# RPi_Color_Detector_LED_PCB_v2.net
KiCad netlist of a schematic drawn in EAGLE
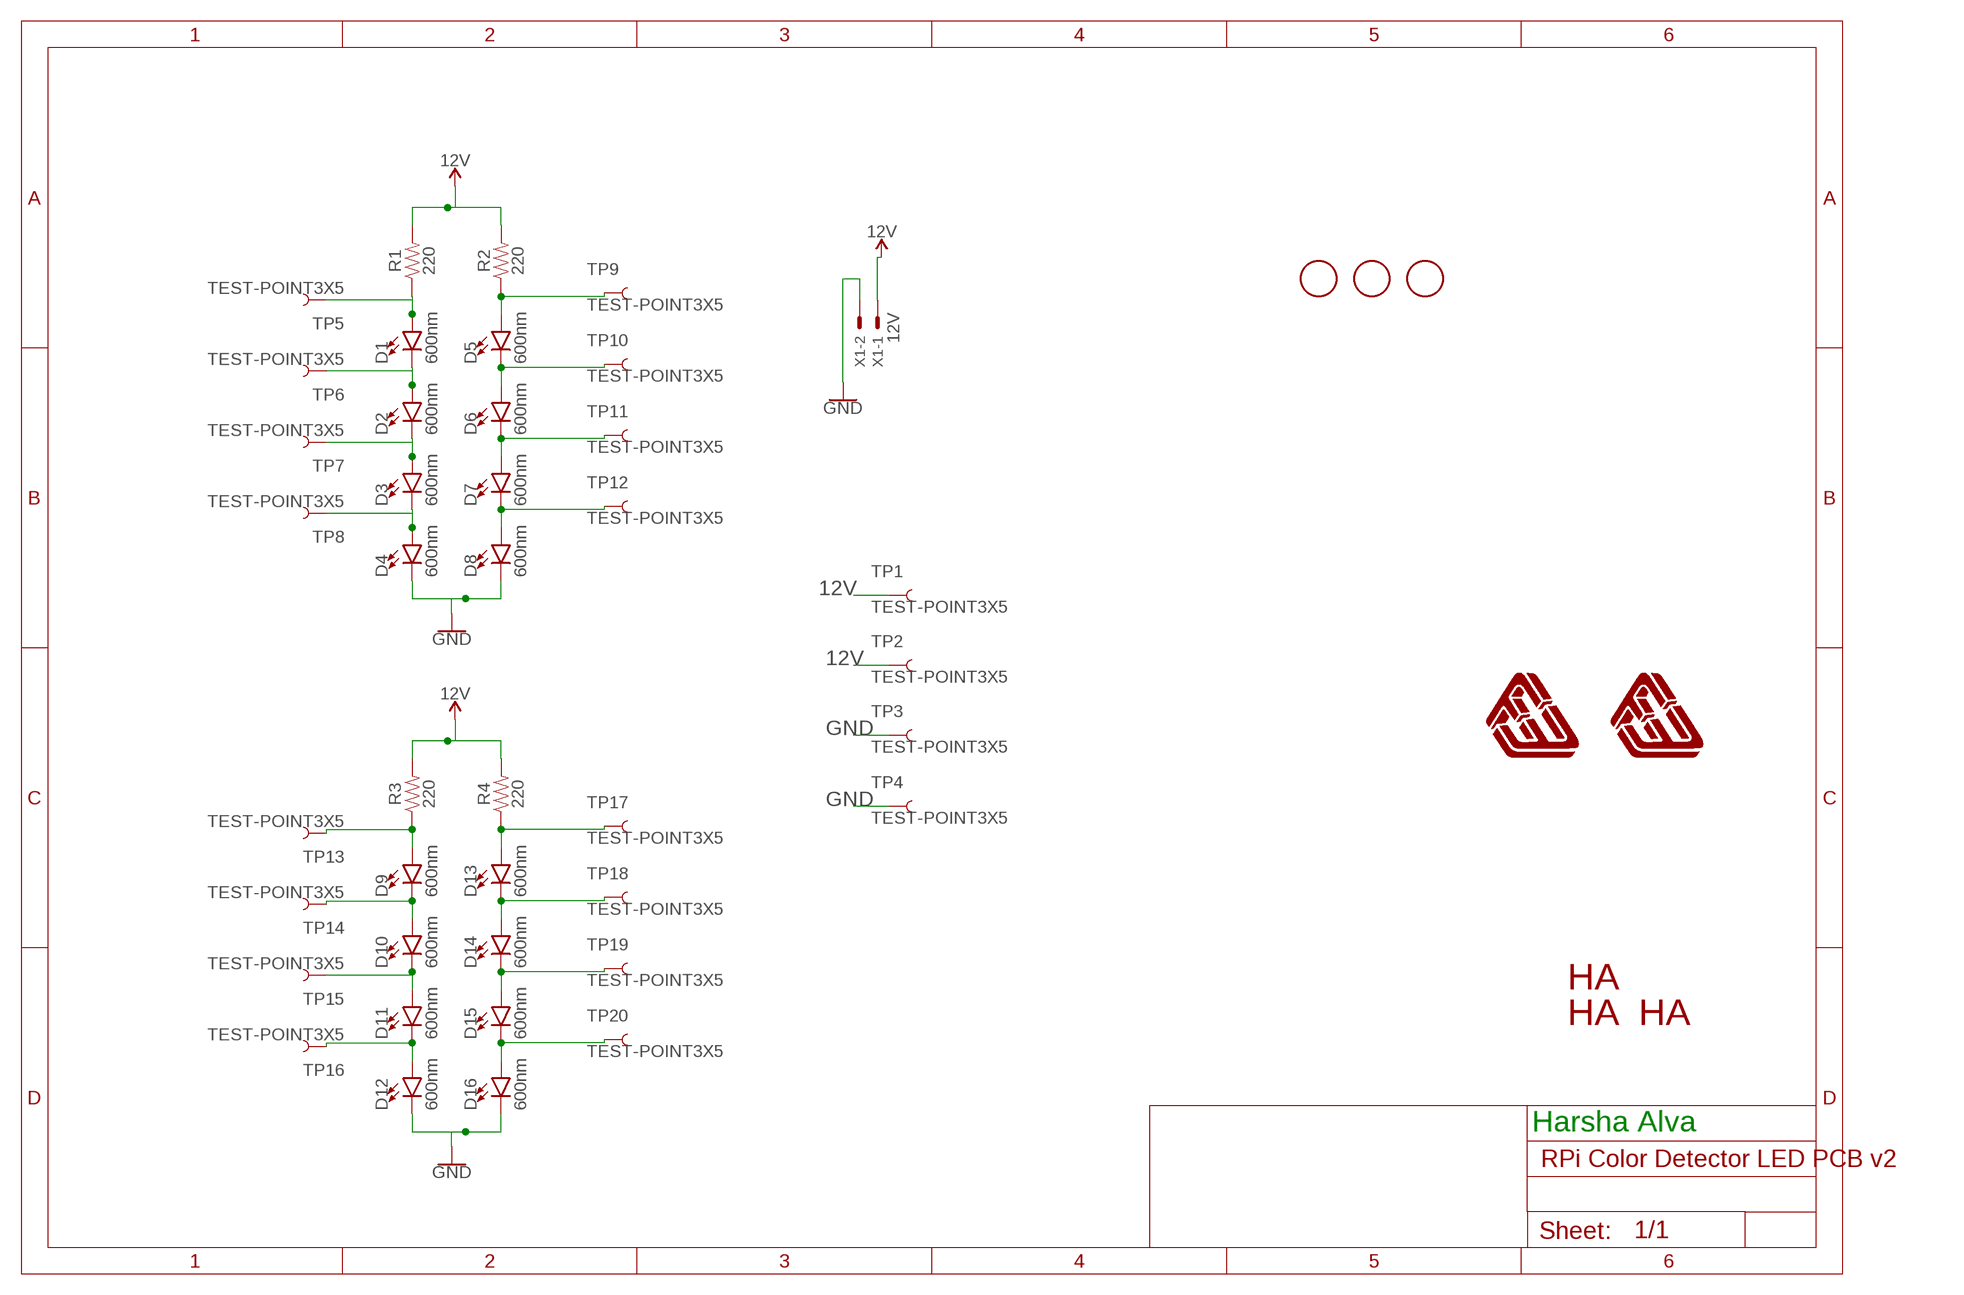
[diagram p0: schematic, sheet 1]

(export (version "E")
  (design (tool "Eeschema 10.0.6"))
  (components
    (comp (ref "D1")
      (value "600nm")
      (footprint "eagle-import:LED-0603")
      (libsource (lib "eagle-import") (part "LED-GREEN0603"))
    )
    (comp (ref "D2")
      (value "600nm")
      (footprint "eagle-import:LED-0603")
      (libsource (lib "eagle-import") (part "LED-GREEN0603"))
    )
    (comp (ref "D3")
      (value "600nm")
      (footprint "eagle-import:LED-0603")
      (libsource (lib "eagle-import") (part "LED-GREEN0603"))
    )
    (comp (ref "D4")
      (value "600nm")
      (footprint "eagle-import:LED-0603")
      (libsource (lib "eagle-import") (part "LED-GREEN0603"))
    )
    (comp (ref "D5")
      (value "600nm")
      (footprint "eagle-import:LED-0603")
      (libsource (lib "eagle-import") (part "LED-GREEN0603"))
    )
    (comp (ref "D6")
      (value "600nm")
      (footprint "eagle-import:LED-0603")
      (libsource (lib "eagle-import") (part "LED-GREEN0603"))
    )
    (comp (ref "D7")
      (value "600nm")
      (footprint "eagle-import:LED-0603")
      (libsource (lib "eagle-import") (part "LED-GREEN0603"))
    )
    (comp (ref "D8")
      (value "600nm")
      (footprint "eagle-import:LED-0603")
      (libsource (lib "eagle-import") (part "LED-GREEN0603"))
    )
    (comp (ref "D9")
      (value "600nm")
      (footprint "eagle-import:LED-0603")
      (libsource (lib "eagle-import") (part "LED-GREEN0603"))
    )
    (comp (ref "D10")
      (value "600nm")
      (footprint "eagle-import:LED-0603")
      (libsource (lib "eagle-import") (part "LED-GREEN0603"))
    )
    (comp (ref "D11")
      (value "600nm")
      (footprint "eagle-import:LED-0603")
      (libsource (lib "eagle-import") (part "LED-GREEN0603"))
    )
    (comp (ref "D12")
      (value "600nm")
      (footprint "eagle-import:LED-0603")
      (libsource (lib "eagle-import") (part "LED-GREEN0603"))
    )
    (comp (ref "D13")
      (value "600nm")
      (footprint "eagle-import:LED-0603")
      (libsource (lib "eagle-import") (part "LED-GREEN0603"))
    )
    (comp (ref "D14")
      (value "600nm")
      (footprint "eagle-import:LED-0603")
      (libsource (lib "eagle-import") (part "LED-GREEN0603"))
    )
    (comp (ref "D15")
      (value "600nm")
      (footprint "eagle-import:LED-0603")
      (libsource (lib "eagle-import") (part "LED-GREEN0603"))
    )
    (comp (ref "D16")
      (value "600nm")
      (footprint "eagle-import:LED-0603")
      (libsource (lib "eagle-import") (part "LED-GREEN0603"))
    )
    (comp (ref "FWLOGO_1")
      (value "FWLOGO")
      (footprint "eagle-import:FWLOGO")
      (libsource (lib "eagle-import") (part "FWLOGO"))
    )
    (comp (ref "FWLOGO_2")
      (value "FWLOGO")
      (footprint "eagle-import:FWLOGO")
      (libsource (lib "eagle-import") (part "FWLOGO"))
    )
    (comp (ref "M_HA_1")
      (value "HA_MARK")
      (footprint "eagle-import:HA_MARK")
      (libsource (lib "eagle-import") (part "HA_MARK"))
    )
    (comp (ref "M_HA_3")
      (value "HA_MARK")
      (footprint "eagle-import:HA_MARK")
      (libsource (lib "eagle-import") (part "HA_MARK"))
    )
    (comp (ref "M_HA_4")
      (value "HA_MARK")
      (footprint "eagle-import:HA_MARK")
      (libsource (lib "eagle-import") (part "HA_MARK"))
    )
    (comp (ref "R1")
      (value "220")
      (footprint "eagle-import:0603")
      (libsource (lib "eagle-import") (part "220OHM-0603-1/10W-1%"))
    )
    (comp (ref "R2")
      (value "220")
      (footprint "eagle-import:0603")
      (libsource (lib "eagle-import") (part "220OHM-0603-1/10W-1%"))
    )
    (comp (ref "R3")
      (value "220")
      (footprint "eagle-import:0603")
      (libsource (lib "eagle-import") (part "220OHM-0603-1/10W-1%"))
    )
    (comp (ref "R4")
      (value "220")
      (footprint "eagle-import:0603")
      (libsource (lib "eagle-import") (part "220OHM-0603-1/10W-1%"))
    )
    (comp (ref "TP1")
      (value "TEST-POINT3X5")
      (footprint "eagle-import:PAD.03X.05")
      (libsource (lib "eagle-import") (part "TEST-POINT3X5"))
    )
    (comp (ref "TP2")
      (value "TEST-POINT3X5")
      (footprint "eagle-import:PAD.03X.05")
      (libsource (lib "eagle-import") (part "TEST-POINT3X5"))
    )
    (comp (ref "TP3")
      (value "TEST-POINT3X5")
      (footprint "eagle-import:PAD.03X.05")
      (libsource (lib "eagle-import") (part "TEST-POINT3X5"))
    )
    (comp (ref "TP4")
      (value "TEST-POINT3X5")
      (footprint "eagle-import:PAD.03X.05")
      (libsource (lib "eagle-import") (part "TEST-POINT3X5"))
    )
    (comp (ref "TP5")
      (value "TEST-POINT3X5")
      (footprint "eagle-import:PAD.03X.05")
      (libsource (lib "eagle-import") (part "TEST-POINT3X5"))
    )
    (comp (ref "TP6")
      (value "TEST-POINT3X5")
      (footprint "eagle-import:PAD.03X.05")
      (libsource (lib "eagle-import") (part "TEST-POINT3X5"))
    )
    (comp (ref "TP7")
      (value "TEST-POINT3X5")
      (footprint "eagle-import:PAD.03X.05")
      (libsource (lib "eagle-import") (part "TEST-POINT3X5"))
    )
    (comp (ref "TP8")
      (value "TEST-POINT3X5")
      (footprint "eagle-import:PAD.03X.05")
      (libsource (lib "eagle-import") (part "TEST-POINT3X5"))
    )
    (comp (ref "TP9")
      (value "TEST-POINT3X5")
      (footprint "eagle-import:PAD.03X.05")
      (libsource (lib "eagle-import") (part "TEST-POINT3X5"))
    )
    (comp (ref "TP10")
      (value "TEST-POINT3X5")
      (footprint "eagle-import:PAD.03X.05")
      (libsource (lib "eagle-import") (part "TEST-POINT3X5"))
    )
    (comp (ref "TP11")
      (value "TEST-POINT3X5")
      (footprint "eagle-import:PAD.03X.05")
      (libsource (lib "eagle-import") (part "TEST-POINT3X5"))
    )
    (comp (ref "TP12")
      (value "TEST-POINT3X5")
      (footprint "eagle-import:PAD.03X.05")
      (libsource (lib "eagle-import") (part "TEST-POINT3X5"))
    )
    (comp (ref "TP13")
      (value "TEST-POINT3X5")
      (footprint "eagle-import:PAD.03X.05")
      (libsource (lib "eagle-import") (part "TEST-POINT3X5"))
    )
    (comp (ref "TP14")
      (value "TEST-POINT3X5")
      (footprint "eagle-import:PAD.03X.05")
      (libsource (lib "eagle-import") (part "TEST-POINT3X5"))
    )
    (comp (ref "TP15")
      (value "TEST-POINT3X5")
      (footprint "eagle-import:PAD.03X.05")
      (libsource (lib "eagle-import") (part "TEST-POINT3X5"))
    )
    (comp (ref "TP16")
      (value "TEST-POINT3X5")
      (footprint "eagle-import:PAD.03X.05")
      (libsource (lib "eagle-import") (part "TEST-POINT3X5"))
    )
    (comp (ref "TP17")
      (value "TEST-POINT3X5")
      (footprint "eagle-import:PAD.03X.05")
      (libsource (lib "eagle-import") (part "TEST-POINT3X5"))
    )
    (comp (ref "TP18")
      (value "TEST-POINT3X5")
      (footprint "eagle-import:PAD.03X.05")
      (libsource (lib "eagle-import") (part "TEST-POINT3X5"))
    )
    (comp (ref "TP19")
      (value "TEST-POINT3X5")
      (footprint "eagle-import:PAD.03X.05")
      (libsource (lib "eagle-import") (part "TEST-POINT3X5"))
    )
    (comp (ref "TP20")
      (value "TEST-POINT3X5")
      (footprint "eagle-import:PAD.03X.05")
      (libsource (lib "eagle-import") (part "TEST-POINT3X5"))
    )
    (comp (ref "U$1")
      (value "FIDUCIAL")
      (footprint "eagle-import:FIDUCIAL_1MM")
      (libsource (lib "eagle-import") (part "FIDUCIAL"))
    )
    (comp (ref "U$2")
      (value "FIDUCIAL")
      (footprint "eagle-import:FIDUCIAL_1MM")
      (libsource (lib "eagle-import") (part "FIDUCIAL"))
    )
    (comp (ref "U$3")
      (value "FIDUCIAL")
      (footprint "eagle-import:FIDUCIAL_1MM")
      (libsource (lib "eagle-import") (part "FIDUCIAL"))
    )
    (comp (ref "X1")
      (value "12V")
      (footprint "eagle-import:JST-XH-02-PACKAGE-LONG-PAD")
      (libsource (lib "eagle-import") (part "JST-XH-02-PIN-LONG-PAD"))
    )
  )
  (nets
    (net (code "1") (name "12V") (class "Default")
      (node (ref "R1") (pin "2") (pinfunction "2_2") (pintype "passive"))
      (node (ref "R2") (pin "2") (pinfunction "2_2") (pintype "passive"))
      (node (ref "R3") (pin "2") (pinfunction "2_2") (pintype "passive"))
      (node (ref "R4") (pin "2") (pinfunction "2_2") (pintype "passive"))
      (node (ref "TP1") (pin "P$1") (pinfunction "1_P$1") (pintype "bidirectional"))
      (node (ref "TP2") (pin "P$1") (pinfunction "1_P$1") (pintype "bidirectional"))
      (node (ref "X1") (pin "1") (pinfunction "S_1") (pintype "passive"))
    )
    (net (code "2") (name "GND") (class "Default")
      (node (ref "D12") (pin "C") (pinfunction "C_C") (pintype "passive"))
      (node (ref "D16") (pin "C") (pinfunction "C_C") (pintype "passive"))
      (node (ref "D4") (pin "C") (pinfunction "C_C") (pintype "passive"))
      (node (ref "D8") (pin "C") (pinfunction "C_C") (pintype "passive"))
      (node (ref "TP3") (pin "P$1") (pinfunction "1_P$1") (pintype "bidirectional"))
      (node (ref "TP4") (pin "P$1") (pinfunction "1_P$1") (pintype "bidirectional"))
      (node (ref "X1") (pin "2") (pinfunction "S_2") (pintype "passive"))
    )
    (net (code "3") (name "Net-(TP5-1)") (class "Default")
      (node (ref "D1") (pin "A") (pinfunction "A_A") (pintype "passive"))
      (node (ref "R1") (pin "1") (pinfunction "1_1") (pintype "passive"))
      (node (ref "TP5") (pin "P$1") (pinfunction "1_P$1") (pintype "bidirectional"))
    )
    (net (code "4") (name "Net-(TP6-1)") (class "Default")
      (node (ref "D1") (pin "C") (pinfunction "C_C") (pintype "passive"))
      (node (ref "D2") (pin "A") (pinfunction "A_A") (pintype "passive"))
      (node (ref "TP6") (pin "P$1") (pinfunction "1_P$1") (pintype "bidirectional"))
    )
    (net (code "5") (name "Net-(TP7-1)") (class "Default")
      (node (ref "D2") (pin "C") (pinfunction "C_C") (pintype "passive"))
      (node (ref "D3") (pin "A") (pinfunction "A_A") (pintype "passive"))
      (node (ref "TP7") (pin "P$1") (pinfunction "1_P$1") (pintype "bidirectional"))
    )
    (net (code "6") (name "Net-(TP8-1)") (class "Default")
      (node (ref "D3") (pin "C") (pinfunction "C_C") (pintype "passive"))
      (node (ref "D4") (pin "A") (pinfunction "A_A") (pintype "passive"))
      (node (ref "TP8") (pin "P$1") (pinfunction "1_P$1") (pintype "bidirectional"))
    )
    (net (code "7") (name "Net-(TP9-1)") (class "Default")
      (node (ref "D5") (pin "A") (pinfunction "A_A") (pintype "passive"))
      (node (ref "R2") (pin "1") (pinfunction "1_1") (pintype "passive"))
      (node (ref "TP9") (pin "P$1") (pinfunction "1_P$1") (pintype "bidirectional"))
    )
    (net (code "8") (name "Net-(TP10-1)") (class "Default")
      (node (ref "D5") (pin "C") (pinfunction "C_C") (pintype "passive"))
      (node (ref "D6") (pin "A") (pinfunction "A_A") (pintype "passive"))
      (node (ref "TP10") (pin "P$1") (pinfunction "1_P$1") (pintype "bidirectional"))
    )
    (net (code "9") (name "Net-(TP11-1)") (class "Default")
      (node (ref "D6") (pin "C") (pinfunction "C_C") (pintype "passive"))
      (node (ref "D7") (pin "A") (pinfunction "A_A") (pintype "passive"))
      (node (ref "TP11") (pin "P$1") (pinfunction "1_P$1") (pintype "bidirectional"))
    )
    (net (code "10") (name "Net-(TP12-1)") (class "Default")
      (node (ref "D7") (pin "C") (pinfunction "C_C") (pintype "passive"))
      (node (ref "D8") (pin "A") (pinfunction "A_A") (pintype "passive"))
      (node (ref "TP12") (pin "P$1") (pinfunction "1_P$1") (pintype "bidirectional"))
    )
    (net (code "11") (name "Net-(TP13-1)") (class "Default")
      (node (ref "D9") (pin "A") (pinfunction "A_A") (pintype "passive"))
      (node (ref "R3") (pin "1") (pinfunction "1_1") (pintype "passive"))
      (node (ref "TP13") (pin "P$1") (pinfunction "1_P$1") (pintype "bidirectional"))
    )
    (net (code "12") (name "Net-(TP14-1)") (class "Default")
      (node (ref "D10") (pin "A") (pinfunction "A_A") (pintype "passive"))
      (node (ref "D9") (pin "C") (pinfunction "C_C") (pintype "passive"))
      (node (ref "TP14") (pin "P$1") (pinfunction "1_P$1") (pintype "bidirectional"))
    )
    (net (code "13") (name "Net-(TP15-1)") (class "Default")
      (node (ref "D10") (pin "C") (pinfunction "C_C") (pintype "passive"))
      (node (ref "D11") (pin "A") (pinfunction "A_A") (pintype "passive"))
      (node (ref "TP15") (pin "P$1") (pinfunction "1_P$1") (pintype "bidirectional"))
    )
    (net (code "14") (name "Net-(TP16-1)") (class "Default")
      (node (ref "D11") (pin "C") (pinfunction "C_C") (pintype "passive"))
      (node (ref "D12") (pin "A") (pinfunction "A_A") (pintype "passive"))
      (node (ref "TP16") (pin "P$1") (pinfunction "1_P$1") (pintype "bidirectional"))
    )
    (net (code "15") (name "Net-(TP17-1)") (class "Default")
      (node (ref "D13") (pin "A") (pinfunction "A_A") (pintype "passive"))
      (node (ref "R4") (pin "1") (pinfunction "1_1") (pintype "passive"))
      (node (ref "TP17") (pin "P$1") (pinfunction "1_P$1") (pintype "bidirectional"))
    )
    (net (code "16") (name "Net-(TP18-1)") (class "Default")
      (node (ref "D13") (pin "C") (pinfunction "C_C") (pintype "passive"))
      (node (ref "D14") (pin "A") (pinfunction "A_A") (pintype "passive"))
      (node (ref "TP18") (pin "P$1") (pinfunction "1_P$1") (pintype "bidirectional"))
    )
    (net (code "17") (name "Net-(TP19-1)") (class "Default")
      (node (ref "D14") (pin "C") (pinfunction "C_C") (pintype "passive"))
      (node (ref "D15") (pin "A") (pinfunction "A_A") (pintype "passive"))
      (node (ref "TP19") (pin "P$1") (pinfunction "1_P$1") (pintype "bidirectional"))
    )
    (net (code "18") (name "Net-(TP20-1)") (class "Default")
      (node (ref "D15") (pin "C") (pinfunction "C_C") (pintype "passive"))
      (node (ref "D16") (pin "A") (pinfunction "A_A") (pintype "passive"))
      (node (ref "TP20") (pin "P$1") (pinfunction "1_P$1") (pintype "bidirectional"))
    )
  )
)
